# Microphone.net
KiCad netlist of a schematic drawn in Altium Designer
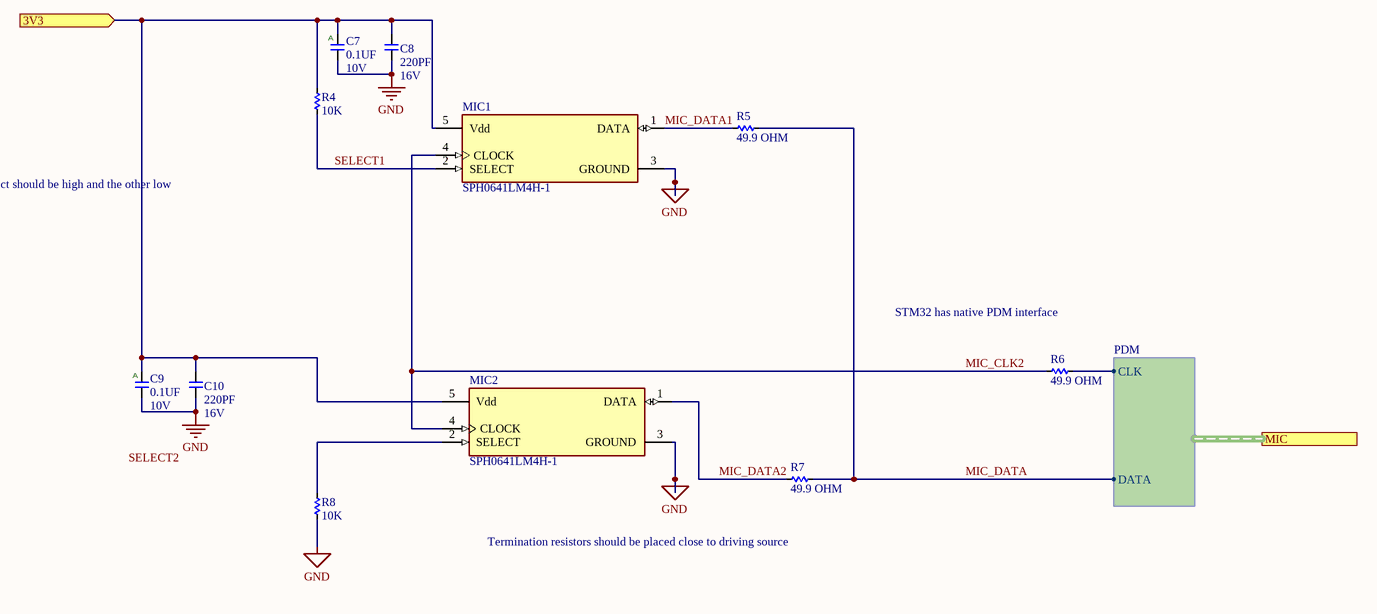
[diagram p0: Microphone.SchDoc]

(export (version "E")
  (design (tool "Eeschema 10.0.6"))
  (components
    (comp (ref "C7")
      (value "0.1UF")
      (footprint "C0201Y")
      (description "CAP, CER, X6S, 0.1uF, 10V, 10%, 0201, AUTOGRADE")
      (fields (field (name "MFG") "MURATA") (field (name "VOLTAGE") "10V") (field (name "TOLERANCE") "10%"))
      (libsource (lib "AltiumReleaseLibDB") (part "__Template_Cap_Auto"))
    )
    (comp (ref "C8")
      (value "220PF")
      (footprint "C0201Y")
      (description "CAP, CER, X7R, 220pF, 16V, 10%, 0201, 0.33mm T")
      (fields (field (name "MFG") "MURATA") (field (name "VOLTAGE") "16V") (field (name "TOLERANCE") "10%"))
      (libsource (lib "AltiumReleaseLibDB") (part "__Template_Cap"))
    )
    (comp (ref "C9")
      (value "0.1UF")
      (footprint "C0201Y")
      (description "CAP, CER, X6S, 0.1uF, 10V, 10%, 0201, AUTOGRADE")
      (fields (field (name "MFG") "MURATA") (field (name "VOLTAGE") "10V") (field (name "TOLERANCE") "10%"))
      (libsource (lib "AltiumReleaseLibDB") (part "__Template_Cap_Auto"))
    )
    (comp (ref "C10")
      (value "220PF")
      (footprint "C0201Y")
      (description "CAP, CER, X7R, 220pF, 16V, 10%, 0201, 0.33mm T")
      (fields (field (name "MFG") "MURATA") (field (name "VOLTAGE") "16V") (field (name "TOLERANCE") "10%"))
      (libsource (lib "AltiumReleaseLibDB") (part "__Template_Cap"))
    )
    (comp (ref "MIC1")
      (value "SPH0641LM4H-1")
      (footprint "FP-SPH0641LM4H-1-MFG")
      (description "MORELLO MIC MULTIMODE DGT BOT PT")
      (libsource (lib "Altium Content Vault") (part "c203a3d83c60dc5a5ebec95f4aed218"))
    )
    (comp (ref "MIC2")
      (value "SPH0641LM4H-1")
      (footprint "FP-SPH0641LM4H-1-MFG")
      (description "MORELLO MIC MULTIMODE DGT BOT PT")
      (libsource (lib "Altium Content Vault") (part "c203a3d83c60dc5a5ebec95f4aed218"))
    )
    (comp (ref "R4")
      (value "10K")
      (footprint "R0201_H0.26MM")
      (description "RES, 10K, 1%, 1/20W, 0201, AUTOGRADE")
      (fields (field (name "MFG") "PANASONIC") (field (name "POWER") "1/20W"))
      (libsource (lib "AltiumReleaseLibDB") (part "__Template_Resistor"))
    )
    (comp (ref "R5")
      (value "49.9 OHM")
      (footprint "R0201_H0.26MM")
      (description "RES, 49.9, 1%, 1/20W, 0201, AUTOGRADE")
      (fields (field (name "MFG") "Panasonic Electronic Components") (field (name "POWER") "0.05W, 1/20W"))
      (libsource (lib "AltiumReleaseLibDB") (part "__Template_Resistor"))
    )
    (comp (ref "R6")
      (value "49.9 OHM")
      (footprint "R0201_H0.26MM")
      (description "RES, 49.9, 1%, 1/20W, 0201, AUTOGRADE")
      (fields (field (name "MFG") "Panasonic Electronic Components") (field (name "POWER") "0.05W, 1/20W"))
      (libsource (lib "AltiumReleaseLibDB") (part "__Template_Resistor"))
    )
    (comp (ref "R7")
      (value "49.9 OHM")
      (footprint "R0201_H0.26MM")
      (description "RES, 49.9, 1%, 1/20W, 0201, AUTOGRADE")
      (fields (field (name "MFG") "Panasonic Electronic Components") (field (name "POWER") "0.05W, 1/20W"))
      (libsource (lib "AltiumReleaseLibDB") (part "__Template_Resistor"))
    )
    (comp (ref "R8")
      (value "10K")
      (footprint "R0201_H0.26MM")
      (description "RES, 10K, 1%, 1/20W, 0201, AUTOGRADE")
      (fields (field (name "MFG") "PANASONIC") (field (name "POWER") "1/20W"))
      (libsource (lib "AltiumReleaseLibDB") (part "__Template_Resistor"))
    )
  )
  (nets
    (net (code "2") (name "/3V3") (class "Default")
      (node (ref "C10") (pin "1") (pintype "passive"))
      (node (ref "C7") (pin "1") (pintype "passive"))
      (node (ref "C8") (pin "1") (pintype "passive"))
      (node (ref "C9") (pin "1") (pintype "passive"))
      (node (ref "MIC1") (pin "5") (pinfunction "Vdd_5") (pintype "power_in"))
      (node (ref "MIC2") (pin "5") (pinfunction "Vdd_5") (pintype "power_in"))
      (node (ref "R4") (pin "2") (pintype "passive"))
    )
    (net (code "3") (name "/CLK") (class "Default") (node (ref "R6") (pin "2") (pintype "passive")))
    (net (code "4") (name "/MIC_CLK2") (class "Default")
      (node (ref "MIC1") (pin "4") (pinfunction "CLOCK_4") (pintype "input"))
      (node (ref "MIC2") (pin "4") (pinfunction "CLOCK_4") (pintype "input"))
      (node (ref "R6") (pin "1") (pintype "passive"))
    )
    (net (code "5") (name "/MIC_DATA") (class "Default")
      (node (ref "R5") (pin "2") (pintype "passive"))
      (node (ref "R7") (pin "2") (pintype "passive"))
    )
    (net (code "6") (name "/MIC_DATA1") (class "Default")
      (node (ref "MIC1") (pin "1") (pinfunction "DATA_1") (pintype "bidirectional"))
      (node (ref "R5") (pin "1") (pintype "passive"))
    )
    (net (code "7") (name "/MIC_DATA2") (class "Default")
      (node (ref "MIC2") (pin "1") (pinfunction "DATA_1") (pintype "bidirectional"))
      (node (ref "R7") (pin "1") (pintype "passive"))
    )
    (net (code "8") (name "/SELECT1") (class "Default")
      (node (ref "MIC1") (pin "2") (pinfunction "SELECT_2") (pintype "input"))
      (node (ref "R4") (pin "1") (pintype "passive"))
    )
    (net (code "11") (name "GND") (class "Default")
      (node (ref "C10") (pin "2") (pintype "passive"))
      (node (ref "C7") (pin "2") (pintype "passive"))
      (node (ref "C8") (pin "2") (pintype "passive"))
      (node (ref "C9") (pin "2") (pintype "passive"))
      (node (ref "MIC1") (pin "3") (pinfunction "GROUND_3") (pintype "power_in"))
      (node (ref "MIC2") (pin "3") (pinfunction "GROUND_3") (pintype "power_in"))
      (node (ref "R8") (pin "1") (pintype "passive"))
    )
    (net (code "12") (name "Net-(MIC2-SELECT)") (class "Default")
      (node (ref "MIC2") (pin "2") (pinfunction "SELECT_2") (pintype "input"))
      (node (ref "R8") (pin "2") (pintype "passive"))
    )
  )
)
